# Arduino_S3v3_R2_a.net
KiCad netlist of a schematic drawn in EAGLE
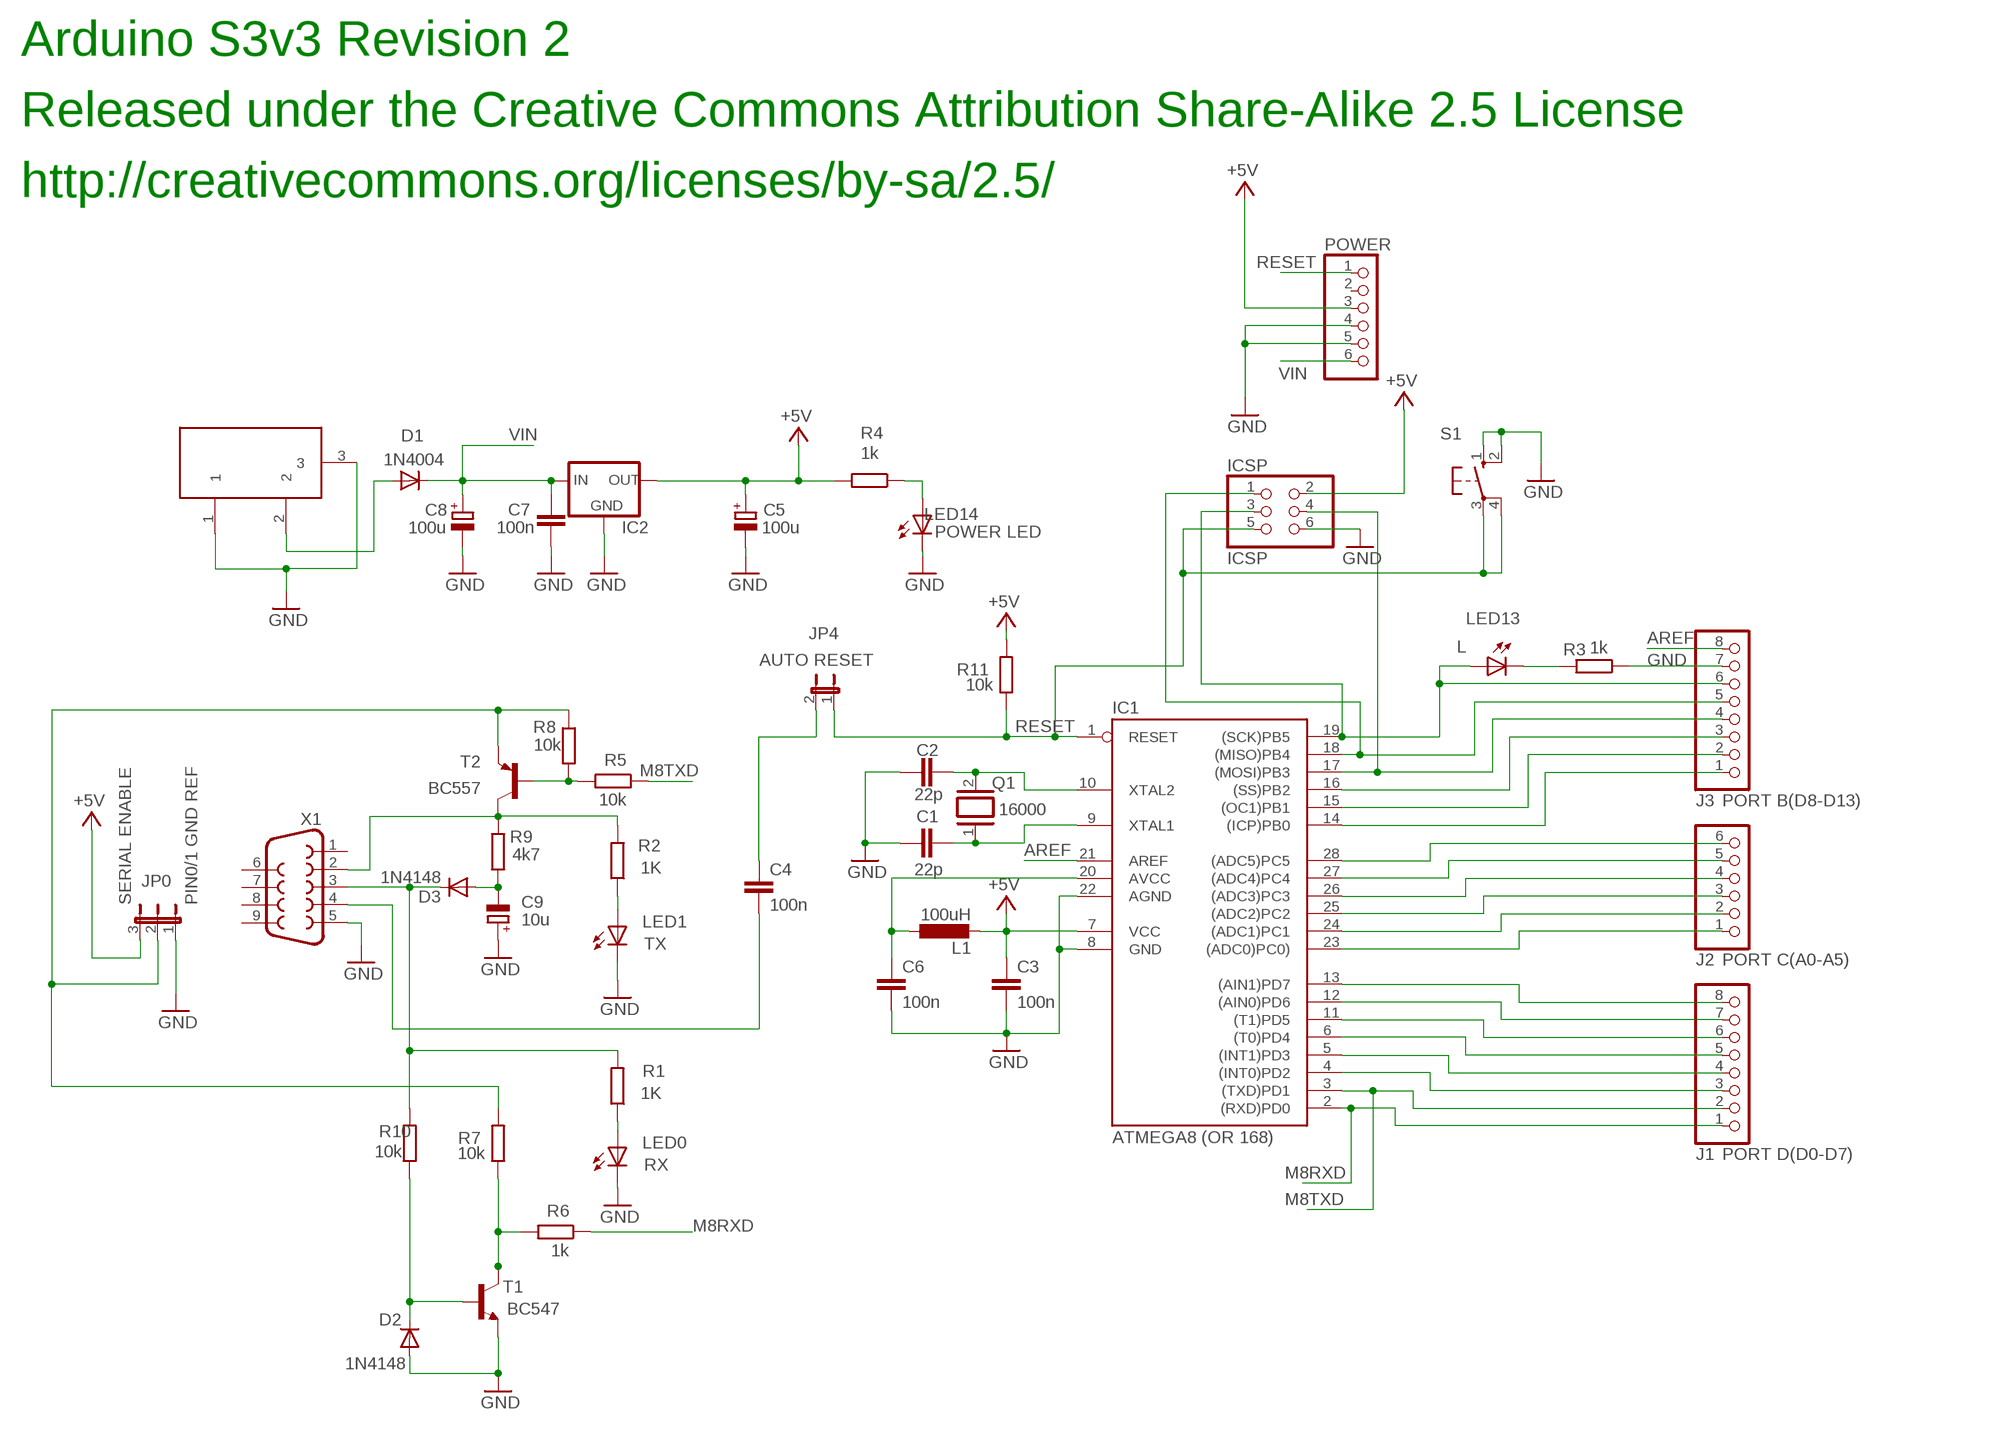
[diagram p0: schematic, sheet 1]

(export (version "E")
  (design (tool "Eeschema 10.0.6"))
  (components
    (comp (ref "C1")
      (value "22p")
      (footprint "eagle-import:C050-025X075")
      (libsource (lib "eagle-import") (part "C-EU050-025X075"))
    )
    (comp (ref "C2")
      (value "22p")
      (footprint "eagle-import:C050-025X075")
      (libsource (lib "eagle-import") (part "C-EU050-025X075"))
    )
    (comp (ref "C3")
      (value "100n")
      (footprint "eagle-import:C050-025X075")
      (libsource (lib "eagle-import") (part "C-EU050-025X075"))
    )
    (comp (ref "C4")
      (value "100n")
      (footprint "eagle-import:C050-025X075")
      (libsource (lib "eagle-import") (part "C-EU050-025X075"))
    )
    (comp (ref "C5")
      (value "100u")
      (footprint "eagle-import:E3,5-8")
      (libsource (lib "eagle-import") (part "CPOL-EUE3.5-8"))
    )
    (comp (ref "C6")
      (value "100n")
      (footprint "eagle-import:C050-025X075")
      (libsource (lib "eagle-import") (part "C-EU050-025X075"))
    )
    (comp (ref "C7")
      (value "100n")
      (footprint "eagle-import:C050-025X075")
      (libsource (lib "eagle-import") (part "C-EU050-025X075"))
    )
    (comp (ref "C8")
      (value "100u")
      (footprint "eagle-import:E3,5-8")
      (libsource (lib "eagle-import") (part "CPOL-EUE3.5-8"))
    )
    (comp (ref "C9")
      (value "10u")
      (footprint "eagle-import:E5-6")
      (libsource (lib "eagle-import") (part "CPOL-EUE5-6"))
    )
    (comp (ref "D1")
      (value "1N4004")
      (footprint "eagle-import:DO41-10")
      (libsource (lib "eagle-import") (part "1N4004"))
    )
    (comp (ref "D2")
      (value "1N4148")
      (footprint "eagle-import:DO35-10")
      (libsource (lib "eagle-import") (part "1N4148"))
    )
    (comp (ref "D3")
      (value "1N4148")
      (footprint "eagle-import:DO35-10")
      (libsource (lib "eagle-import") (part "1N4148"))
    )
    (comp (ref "DC1")
      (value "DC21MMX")
      (footprint "eagle-import:DC-21MM")
      (libsource (lib "eagle-import") (part "DC21MMX"))
    )
    (comp (ref "IC1")
      (value "ATMEGA8 (OR 168)")
      (footprint "eagle-import:DIL28-3")
      (libsource (lib "eagle-import") (part "AT90S4433P"))
    )
    (comp (ref "IC2")
      (value "78XXL")
      (footprint "eagle-import:78XXL")
      (libsource (lib "eagle-import") (part "78XXL"))
    )
    (comp (ref "ICSP")
      (value "ICSP")
      (footprint "eagle-import:2X03")
      (libsource (lib "eagle-import") (part "PINHD-2X3"))
    )
    (comp (ref "J1")
      (value "PORT D(D0-D7)")
      (footprint "eagle-import:1X08")
      (libsource (lib "eagle-import") (part "PINHD-1X8"))
    )
    (comp (ref "J2")
      (value "PORT C(A0-A5)")
      (footprint "eagle-import:1X06")
      (libsource (lib "eagle-import") (part "PINHD-1X6"))
    )
    (comp (ref "J3")
      (value "PORT B(D8-D13)")
      (footprint "eagle-import:1X08")
      (libsource (lib "eagle-import") (part "PINHD-1X8"))
    )
    (comp (ref "JP0")
      (value "JP2W")
      (footprint "eagle-import:JP2W")
      (libsource (lib "eagle-import") (part "JP2W"))
    )
    (comp (ref "JP4")
      (value "AUTO RESET")
      (footprint "eagle-import:JP1W")
      (libsource (lib "eagle-import") (part "JP1W"))
    )
    (comp (ref "L1")
      (value "100uH")
      (footprint "eagle-import:0207_10")
      (libsource (lib "eagle-import") (part "L-EU0207/10"))
    )
    (comp (ref "LED0")
      (value "RX")
      (footprint "eagle-import:LED3MM")
      (libsource (lib "eagle-import") (part "LED3MM"))
    )
    (comp (ref "LED1")
      (value "TX")
      (footprint "eagle-import:LED3MM")
      (libsource (lib "eagle-import") (part "LED3MM"))
    )
    (comp (ref "LED13")
      (value "L")
      (footprint "eagle-import:LED3MM")
      (libsource (lib "eagle-import") (part "LED3MM"))
    )
    (comp (ref "LED14")
      (value "POWER LED")
      (footprint "eagle-import:LED3MM")
      (libsource (lib "eagle-import") (part "LED3MM"))
    )
    (comp (ref "POWER")
      (value "PINHD-1X6")
      (footprint "eagle-import:1X06")
      (libsource (lib "eagle-import") (part "PINHD-1X6"))
    )
    (comp (ref "Q1")
      (value "16000")
      (footprint "eagle-import:Q")
      (libsource (lib "eagle-import") (part "XTAL"))
    )
    (comp (ref "R1")
      (value "1K")
      (footprint "eagle-import:0207_10")
      (libsource (lib "eagle-import") (part "R-EU_0207/10"))
    )
    (comp (ref "R2")
      (value "1K")
      (footprint "eagle-import:0207_10")
      (libsource (lib "eagle-import") (part "R-EU_0207/10"))
    )
    (comp (ref "R3")
      (value "1k")
      (footprint "eagle-import:0207_10")
      (libsource (lib "eagle-import") (part "R-EU_0207/10"))
    )
    (comp (ref "R4")
      (value "1k")
      (footprint "eagle-import:0207_10")
      (libsource (lib "eagle-import") (part "R-EU_0207/10"))
    )
    (comp (ref "R5")
      (value "10k")
      (footprint "eagle-import:0207_10")
      (libsource (lib "eagle-import") (part "R-EU_0207/10"))
    )
    (comp (ref "R6")
      (value "1k")
      (footprint "eagle-import:0207_10")
      (libsource (lib "eagle-import") (part "R-EU_0207/10"))
    )
    (comp (ref "R7")
      (value "10k")
      (footprint "eagle-import:0207_10")
      (libsource (lib "eagle-import") (part "R-EU_0207/10"))
    )
    (comp (ref "R8")
      (value "10k")
      (footprint "eagle-import:0207_10")
      (libsource (lib "eagle-import") (part "R-EU_0207/10"))
    )
    (comp (ref "R9")
      (value "4k7")
      (footprint "eagle-import:0207_10")
      (libsource (lib "eagle-import") (part "R-EU_0207/10"))
    )
    (comp (ref "R10")
      (value "10k")
      (footprint "eagle-import:0207_10")
      (libsource (lib "eagle-import") (part "R-EU_0207/10"))
    )
    (comp (ref "R11")
      (value "10k")
      (footprint "eagle-import:0207_10")
      (libsource (lib "eagle-import") (part "R-EU_0207/10"))
    )
    (comp (ref "S1")
      (value "10-XX")
      (footprint "eagle-import:B3F-10XX")
      (libsource (lib "eagle-import") (part "10-XX"))
    )
    (comp (ref "T1")
      (value "BC547")
      (footprint "eagle-import:TO92")
      (libsource (lib "eagle-import") (part "BC547"))
    )
    (comp (ref "T2")
      (value "BC557")
      (footprint "eagle-import:TO92-EBC")
      (libsource (lib "eagle-import") (part "-PNP-TO92-EBCBC557B"))
    )
    (comp (ref "X1")
      (value "F09H")
      (footprint "eagle-import:F09H")
      (libsource (lib "eagle-import") (part "F09H"))
    )
  )
  (nets
    (net (code "1") (name "+5V") (class "Default")
      (node (ref "C3") (pin "1") (pinfunction "1_1") (pintype "passive"))
      (node (ref "C5") (pin "+") (pinfunction "+_+") (pintype "passive"))
      (node (ref "IC1") (pin "7") (pinfunction "VCC_7") (pintype "power_in"))
      (node (ref "IC2") (pin "OUT") (pinfunction "OUT_OUT") (pintype "passive"))
      (node (ref "ICSP") (pin "2") (pinfunction "2_2") (pintype "passive"))
      (node (ref "JP0") (pin "3") (pinfunction "3_3") (pintype "passive"))
      (node (ref "L1") (pin "2") (pinfunction "2_2") (pintype "passive"))
      (node (ref "POWER") (pin "3") (pinfunction "3_3") (pintype "passive"))
      (node (ref "R11") (pin "2") (pinfunction "2_2") (pintype "passive"))
      (node (ref "R4") (pin "2") (pinfunction "2_2") (pintype "passive"))
    )
    (net (code "2") (name "/AREF") (class "Default")
      (node (ref "IC1") (pin "21") (pinfunction "AREF_21") (pintype "power_in"))
      (node (ref "J3") (pin "8") (pinfunction "8_8") (pintype "passive"))
    )
    (net (code "3") (name "/M8RXD") (class "Default")
      (node (ref "IC1") (pin "2") (pinfunction "(RXD)PD0_2") (pintype "bidirectional"))
      (node (ref "J1") (pin "1") (pinfunction "1_1") (pintype "passive"))
      (node (ref "R6") (pin "1") (pinfunction "1_1") (pintype "passive"))
    )
    (net (code "4") (name "/M8TXD") (class "Default")
      (node (ref "IC1") (pin "3") (pinfunction "(TXD)PD1_3") (pintype "bidirectional"))
      (node (ref "J1") (pin "2") (pinfunction "2_2") (pintype "passive"))
      (node (ref "R5") (pin "1") (pinfunction "1_1") (pintype "passive"))
    )
    (net (code "5") (name "/RESET") (class "Default")
      (node (ref "IC1") (pin "1") (pinfunction "RESET_1") (pintype "input"))
      (node (ref "ICSP") (pin "5") (pinfunction "5_5") (pintype "passive"))
      (node (ref "JP4") (pin "1") (pinfunction "1_1") (pintype "passive"))
      (node (ref "POWER") (pin "1") (pinfunction "1_1") (pintype "passive"))
      (node (ref "R11") (pin "1") (pinfunction "1_1") (pintype "passive"))
      (node (ref "S1") (pin "3") (pinfunction "P_3") (pintype "passive"))
      (node (ref "S1") (pin "4") (pinfunction "P1_4") (pintype "passive"))
    )
    (net (code "6") (name "/VIN") (class "Default")
      (node (ref "C7") (pin "2") (pinfunction "2_2") (pintype "passive"))
      (node (ref "C8") (pin "+") (pinfunction "+_+") (pintype "passive"))
      (node (ref "D1") (pin "C") (pinfunction "C_C") (pintype "passive"))
      (node (ref "IC2") (pin "IN") (pinfunction "IN_IN") (pintype "input"))
      (node (ref "POWER") (pin "6") (pinfunction "6_6") (pintype "passive"))
    )
    (net (code "7") (name "GND") (class "Default")
      (node (ref "C1") (pin "1") (pinfunction "1_1") (pintype "passive"))
      (node (ref "C2") (pin "1") (pinfunction "1_1") (pintype "passive"))
      (node (ref "C3") (pin "2") (pinfunction "2_2") (pintype "passive"))
      (node (ref "C5") (pin "-") (pinfunction "-_-") (pintype "passive"))
      (node (ref "C6") (pin "2") (pinfunction "2_2") (pintype "passive"))
      (node (ref "C7") (pin "1") (pinfunction "1_1") (pintype "passive"))
      (node (ref "C8") (pin "-") (pinfunction "-_-") (pintype "passive"))
      (node (ref "C9") (pin "+") (pinfunction "+_+") (pintype "passive"))
      (node (ref "D2") (pin "A") (pinfunction "A_A") (pintype "passive"))
      (node (ref "DC1") (pin "1") (pinfunction "1_1") (pintype "power_in"))
      (node (ref "DC1") (pin "3") (pinfunction "3_3") (pintype "power_in"))
      (node (ref "IC1") (pin "22") (pinfunction "AGND_22") (pintype "power_in"))
      (node (ref "IC1") (pin "8") (pinfunction "GND_8") (pintype "power_in"))
      (node (ref "IC2") (pin "GND") (pinfunction "GND_GND") (pintype "input"))
      (node (ref "ICSP") (pin "6") (pinfunction "6_6") (pintype "passive"))
      (node (ref "J3") (pin "7") (pinfunction "7_7") (pintype "passive"))
      (node (ref "JP0") (pin "1") (pinfunction "1_1") (pintype "passive"))
      (node (ref "LED0") (pin "K") (pinfunction "C_K") (pintype "passive"))
      (node (ref "LED1") (pin "K") (pinfunction "C_K") (pintype "passive"))
      (node (ref "LED14") (pin "K") (pinfunction "C_K") (pintype "passive"))
      (node (ref "POWER") (pin "4") (pinfunction "4_4") (pintype "passive"))
      (node (ref "POWER") (pin "5") (pinfunction "5_5") (pintype "passive"))
      (node (ref "R3") (pin "1") (pinfunction "1_1") (pintype "passive"))
      (node (ref "S1") (pin "1") (pinfunction "S_1") (pintype "passive"))
      (node (ref "S1") (pin "2") (pinfunction "S1_2") (pintype "passive"))
      (node (ref "T1") (pin "1") (pinfunction "E_1") (pintype "passive"))
      (node (ref "X1") (pin "5") (pinfunction "5_5") (pintype "passive"))
    )
    (net (code "8") (name "Net-(C4-Pad1)") (class "Default")
      (node (ref "C4") (pin "1") (pinfunction "1_1") (pintype "passive"))
      (node (ref "JP4") (pin "2") (pinfunction "2_2") (pintype "passive"))
    )
    (net (code "9") (name "Net-(C4-Pad2)") (class "Default")
      (node (ref "C4") (pin "2") (pinfunction "2_2") (pintype "passive"))
      (node (ref "X1") (pin "4") (pinfunction "4_4") (pintype "passive"))
    )
    (net (code "10") (name "Net-(C9-Pad-)") (class "Default")
      (node (ref "C9") (pin "-") (pinfunction "-_-") (pintype "passive"))
      (node (ref "D3") (pin "A") (pinfunction "A_A") (pintype "passive"))
      (node (ref "R9") (pin "1") (pinfunction "1_1") (pintype "passive"))
    )
    (net (code "11") (name "Net-(D1-PadA)") (class "Default")
      (node (ref "D1") (pin "A") (pinfunction "A_A") (pintype "passive"))
      (node (ref "DC1") (pin "2") (pinfunction "2_2") (pintype "power_in"))
    )
    (net (code "12") (name "Net-(D3-PadC)") (class "Default")
      (node (ref "D3") (pin "C") (pinfunction "C_C") (pintype "passive"))
      (node (ref "R1") (pin "2") (pinfunction "2_2") (pintype "passive"))
      (node (ref "R10") (pin "2") (pinfunction "2_2") (pintype "passive"))
      (node (ref "X1") (pin "3") (pinfunction "3_3") (pintype "passive"))
    )
    (net (code "13") (name "Net-(IC1-(ADC0)PC0))") (class "Default")
      (node (ref "IC1") (pin "23") (pinfunction "(ADC0)PC0)_23") (pintype "bidirectional"))
      (node (ref "J2") (pin "1") (pinfunction "1_1") (pintype "passive"))
    )
    (net (code "14") (name "Net-(IC1-(ADC1)PC1)") (class "Default")
      (node (ref "IC1") (pin "24") (pinfunction "(ADC1)PC1_24") (pintype "bidirectional"))
      (node (ref "J2") (pin "2") (pinfunction "2_2") (pintype "passive"))
    )
    (net (code "15") (name "Net-(IC1-(ADC2)PC2)") (class "Default")
      (node (ref "IC1") (pin "25") (pinfunction "(ADC2)PC2_25") (pintype "bidirectional"))
      (node (ref "J2") (pin "3") (pinfunction "3_3") (pintype "passive"))
    )
    (net (code "16") (name "Net-(IC1-(ADC3)PC3)") (class "Default")
      (node (ref "IC1") (pin "26") (pinfunction "(ADC3)PC3_26") (pintype "bidirectional"))
      (node (ref "J2") (pin "4") (pinfunction "4_4") (pintype "passive"))
    )
    (net (code "17") (name "Net-(IC1-(ADC4)PC4)") (class "Default")
      (node (ref "IC1") (pin "27") (pinfunction "(ADC4)PC4_27") (pintype "bidirectional"))
      (node (ref "J2") (pin "5") (pinfunction "5_5") (pintype "passive"))
    )
    (net (code "18") (name "Net-(IC1-(ADC5)PC5)") (class "Default")
      (node (ref "IC1") (pin "28") (pinfunction "(ADC5)PC5_28") (pintype "bidirectional"))
      (node (ref "J2") (pin "6") (pinfunction "6_6") (pintype "passive"))
    )
    (net (code "19") (name "Net-(IC1-(AIN0)PD6)") (class "Default")
      (node (ref "IC1") (pin "12") (pinfunction "(AIN0)PD6_12") (pintype "bidirectional"))
      (node (ref "J1") (pin "7") (pinfunction "7_7") (pintype "passive"))
    )
    (net (code "20") (name "Net-(IC1-(AIN1)PD7)") (class "Default")
      (node (ref "IC1") (pin "13") (pinfunction "(AIN1)PD7_13") (pintype "bidirectional"))
      (node (ref "J1") (pin "8") (pinfunction "8_8") (pintype "passive"))
    )
    (net (code "21") (name "Net-(IC1-(ICP)PB0)") (class "Default")
      (node (ref "IC1") (pin "14") (pinfunction "(ICP)PB0_14") (pintype "bidirectional"))
      (node (ref "J3") (pin "1") (pinfunction "1_1") (pintype "passive"))
    )
    (net (code "22") (name "Net-(IC1-(INT0)PD2)") (class "Default")
      (node (ref "IC1") (pin "4") (pinfunction "(INT0)PD2_4") (pintype "bidirectional"))
      (node (ref "J1") (pin "3") (pinfunction "3_3") (pintype "passive"))
    )
    (net (code "23") (name "Net-(IC1-(INT1)PD3)") (class "Default")
      (node (ref "IC1") (pin "5") (pinfunction "(INT1)PD3_5") (pintype "bidirectional"))
      (node (ref "J1") (pin "4") (pinfunction "4_4") (pintype "passive"))
    )
    (net (code "24") (name "Net-(IC1-(MISO)PB4)") (class "Default")
      (node (ref "IC1") (pin "18") (pinfunction "(MISO)PB4_18") (pintype "bidirectional"))
      (node (ref "ICSP") (pin "1") (pinfunction "1_1") (pintype "passive"))
      (node (ref "J3") (pin "5") (pinfunction "5_5") (pintype "passive"))
    )
    (net (code "25") (name "Net-(IC1-(MOSI)PB3)") (class "Default")
      (node (ref "IC1") (pin "17") (pinfunction "(MOSI)PB3_17") (pintype "bidirectional"))
      (node (ref "ICSP") (pin "4") (pinfunction "4_4") (pintype "passive"))
      (node (ref "J3") (pin "4") (pinfunction "4_4") (pintype "passive"))
    )
    (net (code "26") (name "Net-(IC1-(OC1)PB1)") (class "Default")
      (node (ref "IC1") (pin "15") (pinfunction "(OC1)PB1_15") (pintype "bidirectional"))
      (node (ref "J3") (pin "2") (pinfunction "2_2") (pintype "passive"))
    )
    (net (code "27") (name "Net-(IC1-(SCK)PB5)") (class "Default")
      (node (ref "IC1") (pin "19") (pinfunction "(SCK)PB5_19") (pintype "bidirectional"))
      (node (ref "ICSP") (pin "3") (pinfunction "3_3") (pintype "passive"))
      (node (ref "J3") (pin "6") (pinfunction "6_6") (pintype "passive"))
      (node (ref "LED13") (pin "A") (pinfunction "A_A") (pintype "passive"))
    )
    (net (code "28") (name "Net-(IC1-(SS)PB2)") (class "Default")
      (node (ref "IC1") (pin "16") (pinfunction "(SS)PB2_16") (pintype "bidirectional"))
      (node (ref "J3") (pin "3") (pinfunction "3_3") (pintype "passive"))
    )
    (net (code "29") (name "Net-(IC1-(T0)PD4)") (class "Default")
      (node (ref "IC1") (pin "6") (pinfunction "(T0)PD4_6") (pintype "bidirectional"))
      (node (ref "J1") (pin "5") (pinfunction "5_5") (pintype "passive"))
    )
    (net (code "30") (name "Net-(IC1-(T1)PD5)") (class "Default")
      (node (ref "IC1") (pin "11") (pinfunction "(T1)PD5_11") (pintype "bidirectional"))
      (node (ref "J1") (pin "6") (pinfunction "6_6") (pintype "passive"))
    )
    (net (code "31") (name "Net-(IC1-AVCC)") (class "Default")
      (node (ref "C6") (pin "1") (pinfunction "1_1") (pintype "passive"))
      (node (ref "IC1") (pin "20") (pinfunction "AVCC_20") (pintype "power_in"))
      (node (ref "L1") (pin "1") (pinfunction "1_1") (pintype "passive"))
    )
    (net (code "32") (name "Net-(IC1-XTAL1)") (class "Default")
      (node (ref "C1") (pin "2") (pinfunction "2_2") (pintype "passive"))
      (node (ref "IC1") (pin "9") (pinfunction "XTAL1_9") (pintype "bidirectional"))
      (node (ref "Q1") (pin "1") (pinfunction "1_1") (pintype "passive"))
    )
    (net (code "33") (name "Net-(IC1-XTAL2)") (class "Default")
      (node (ref "C2") (pin "2") (pinfunction "2_2") (pintype "passive"))
      (node (ref "IC1") (pin "10") (pinfunction "XTAL2_10") (pintype "bidirectional"))
      (node (ref "Q1") (pin "2") (pinfunction "2_2") (pintype "passive"))
    )
    (net (code "34") (name "Net-(JP0-Pad2)") (class "Default")
      (node (ref "JP0") (pin "2") (pinfunction "2_2") (pintype "passive"))
      (node (ref "R7") (pin "2") (pinfunction "2_2") (pintype "passive"))
      (node (ref "R8") (pin "1") (pinfunction "1_1") (pintype "passive"))
      (node (ref "T2") (pin "E") (pinfunction "E_E") (pintype "passive"))
    )
    (net (code "35") (name "Net-(LED0-PadA)") (class "Default")
      (node (ref "LED0") (pin "A") (pinfunction "A_A") (pintype "passive"))
      (node (ref "R1") (pin "1") (pinfunction "1_1") (pintype "passive"))
    )
    (net (code "36") (name "Net-(LED1-PadA)") (class "Default")
      (node (ref "LED1") (pin "A") (pinfunction "A_A") (pintype "passive"))
      (node (ref "R2") (pin "1") (pinfunction "1_1") (pintype "passive"))
    )
    (net (code "37") (name "Net-(LED13-C)") (class "Default")
      (node (ref "LED13") (pin "K") (pinfunction "C_K") (pintype "passive"))
      (node (ref "R3") (pin "2") (pinfunction "2_2") (pintype "passive"))
    )
    (net (code "38") (name "Net-(LED14-PadA)") (class "Default")
      (node (ref "LED14") (pin "A") (pinfunction "A_A") (pintype "passive"))
      (node (ref "R4") (pin "1") (pinfunction "1_1") (pintype "passive"))
    )
    (net (code "39") (name "Net-(R2-Pad2)") (class "Default")
      (node (ref "R2") (pin "2") (pinfunction "2_2") (pintype "passive"))
      (node (ref "R9") (pin "2") (pinfunction "2_2") (pintype "passive"))
      (node (ref "T2") (pin "C") (pinfunction "C_C") (pintype "passive"))
      (node (ref "X1") (pin "2") (pinfunction "2_2") (pintype "passive"))
    )
    (net (code "40") (name "Net-(R5-Pad2)") (class "Default")
      (node (ref "R5") (pin "2") (pinfunction "2_2") (pintype "passive"))
      (node (ref "R8") (pin "2") (pinfunction "2_2") (pintype "passive"))
      (node (ref "T2") (pin "B") (pinfunction "B_B") (pintype "passive"))
    )
    (net (code "41") (name "Net-(T1-B)") (class "Default")
      (node (ref "D2") (pin "C") (pinfunction "C_C") (pintype "passive"))
      (node (ref "R10") (pin "1") (pinfunction "1_1") (pintype "passive"))
      (node (ref "T1") (pin "2") (pinfunction "B_2") (pintype "passive"))
    )
    (net (code "42") (name "Net-(T1-C)") (class "Default")
      (node (ref "R6") (pin "2") (pinfunction "2_2") (pintype "passive"))
      (node (ref "R7") (pin "1") (pinfunction "1_1") (pintype "passive"))
      (node (ref "T1") (pin "3") (pinfunction "C_3") (pintype "passive"))
    )
    (net (code "43") (name "unconnected-(POWER-Pad2)") (class "Default")
      (node (ref "POWER") (pin "2") (pinfunction "2_2") (pintype "passive"))
    )
    (net (code "44") (name "unconnected-(X1-Pad1)") (class "Default")
      (node (ref "X1") (pin "1") (pinfunction "1_1") (pintype "passive"))
    )
    (net (code "45") (name "unconnected-(X1-Pad6)") (class "Default")
      (node (ref "X1") (pin "6") (pinfunction "6_6") (pintype "passive"))
    )
    (net (code "46") (name "unconnected-(X1-Pad7)") (class "Default")
      (node (ref "X1") (pin "7") (pinfunction "7_7") (pintype "passive"))
    )
    (net (code "47") (name "unconnected-(X1-Pad8)") (class "Default")
      (node (ref "X1") (pin "8") (pinfunction "8_8") (pintype "passive"))
    )
    (net (code "48") (name "unconnected-(X1-Pad9)") (class "Default")
      (node (ref "X1") (pin "9") (pinfunction "9_9") (pintype "passive"))
    )
  )
)
